# dig_ac230.net
KiCad netlist of a schematic drawn in EAGLE
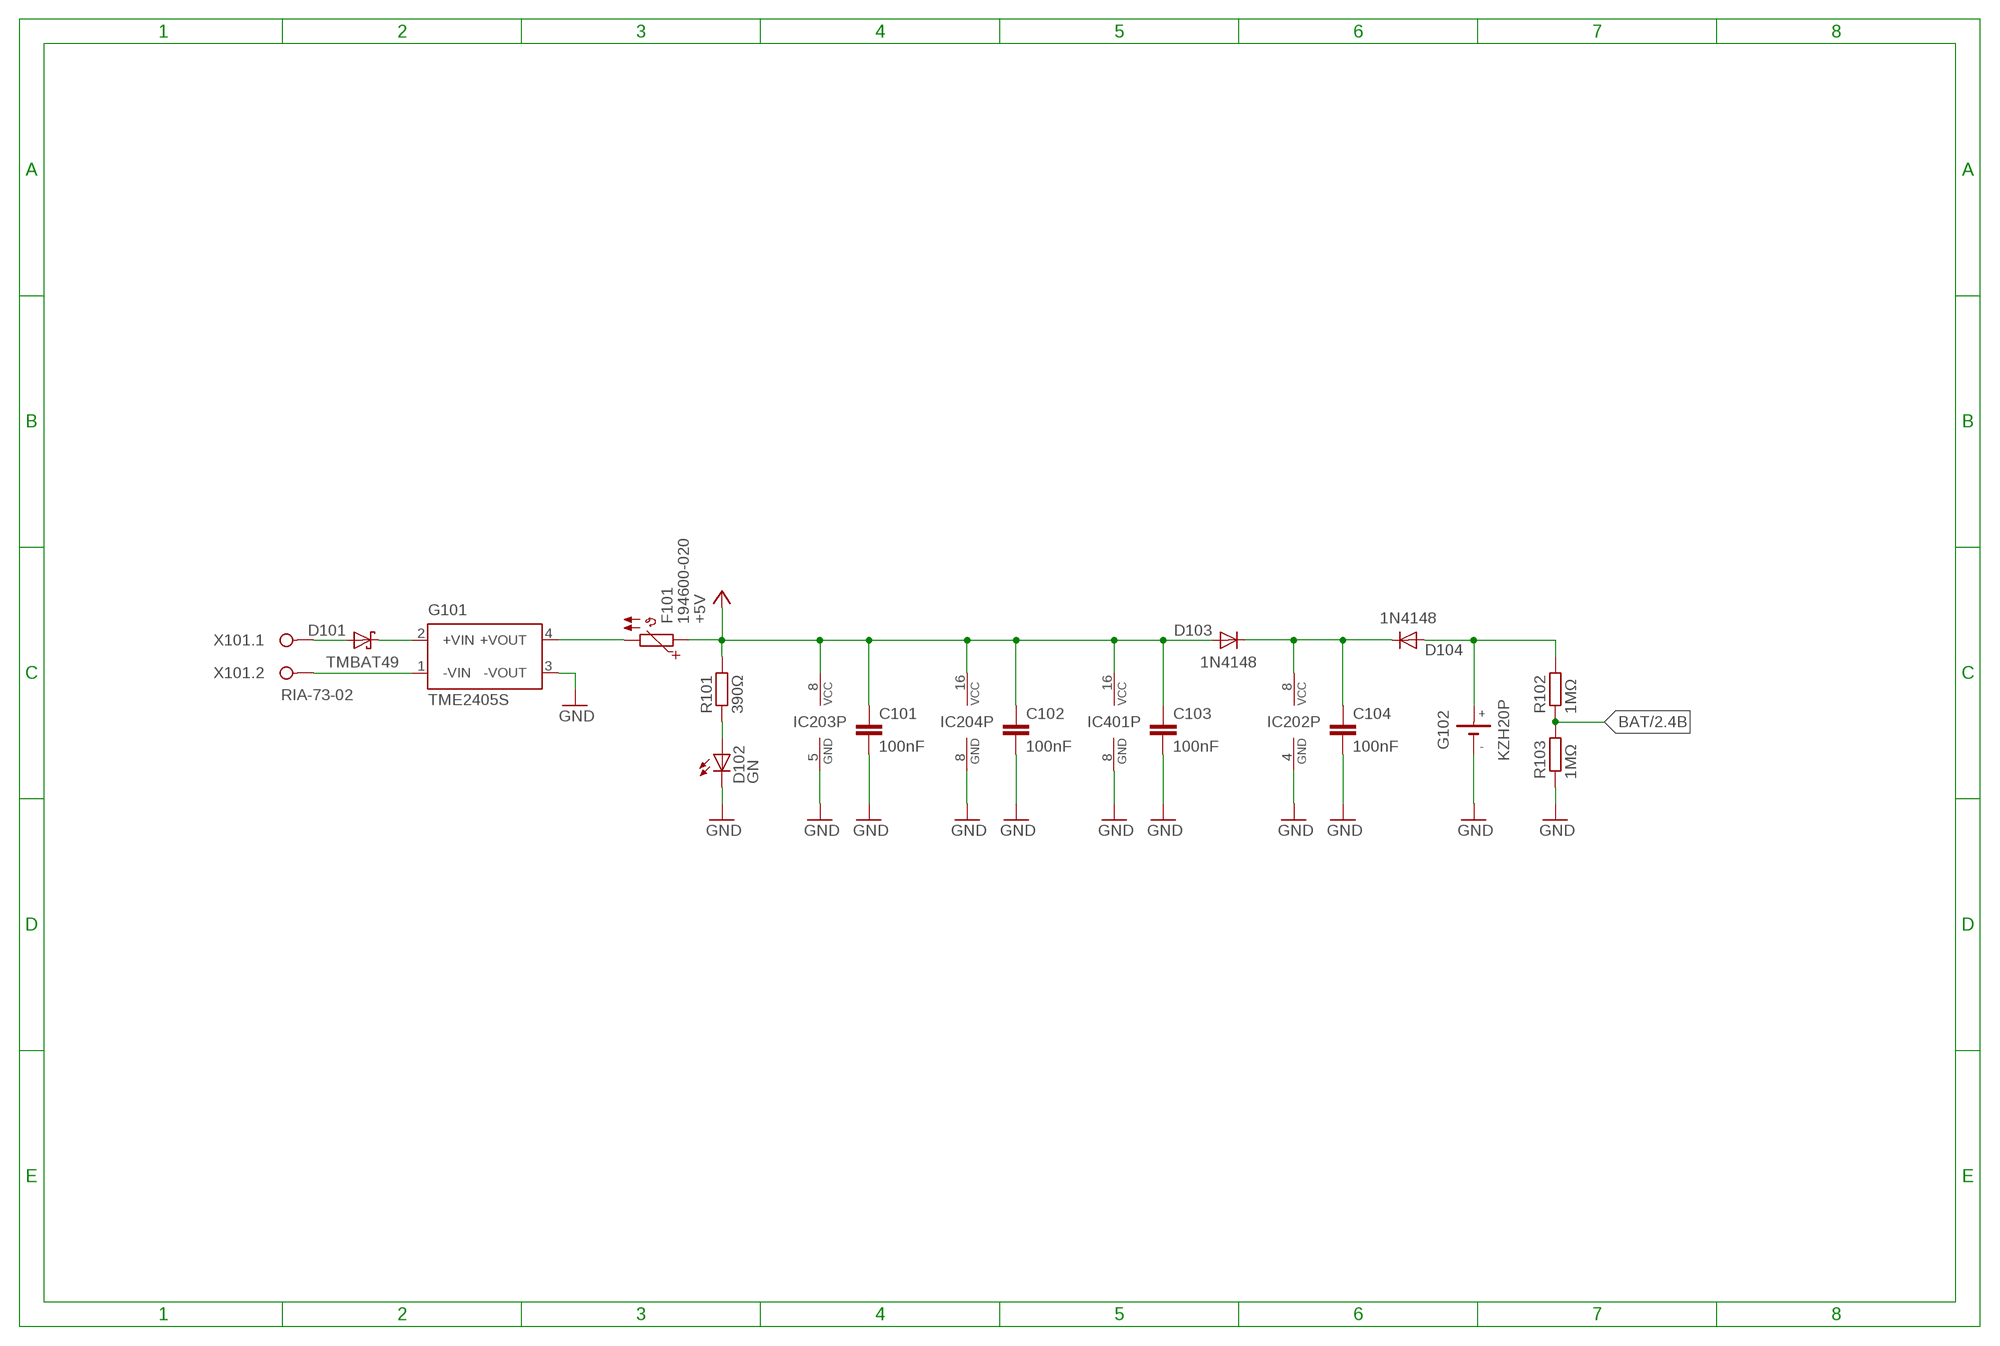
[diagram p0: schematic, sheet 1]
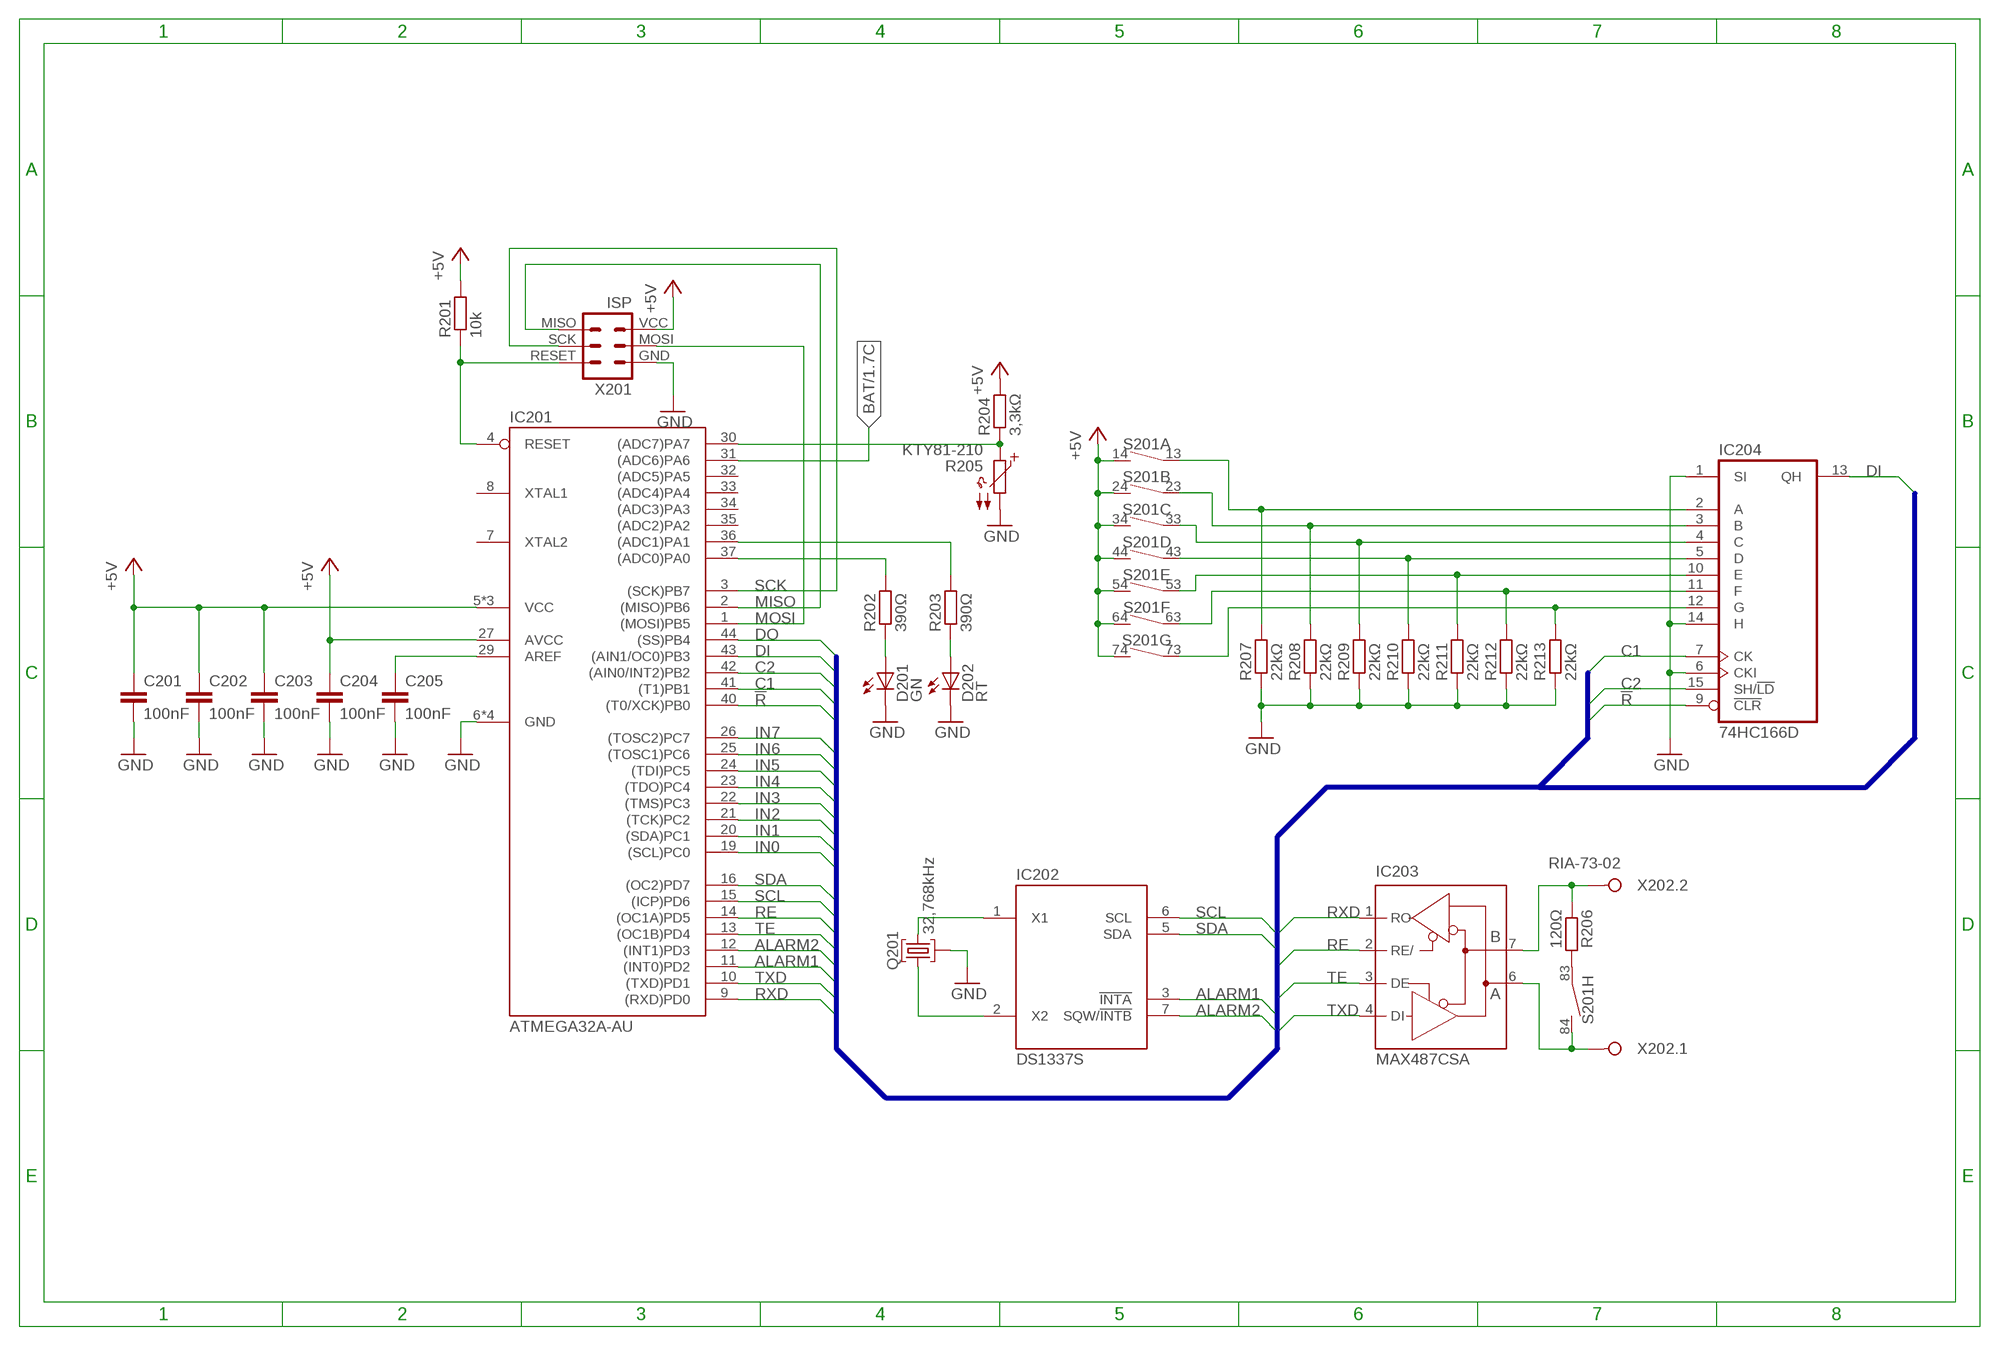
[diagram p1: schematic, sheet 2]
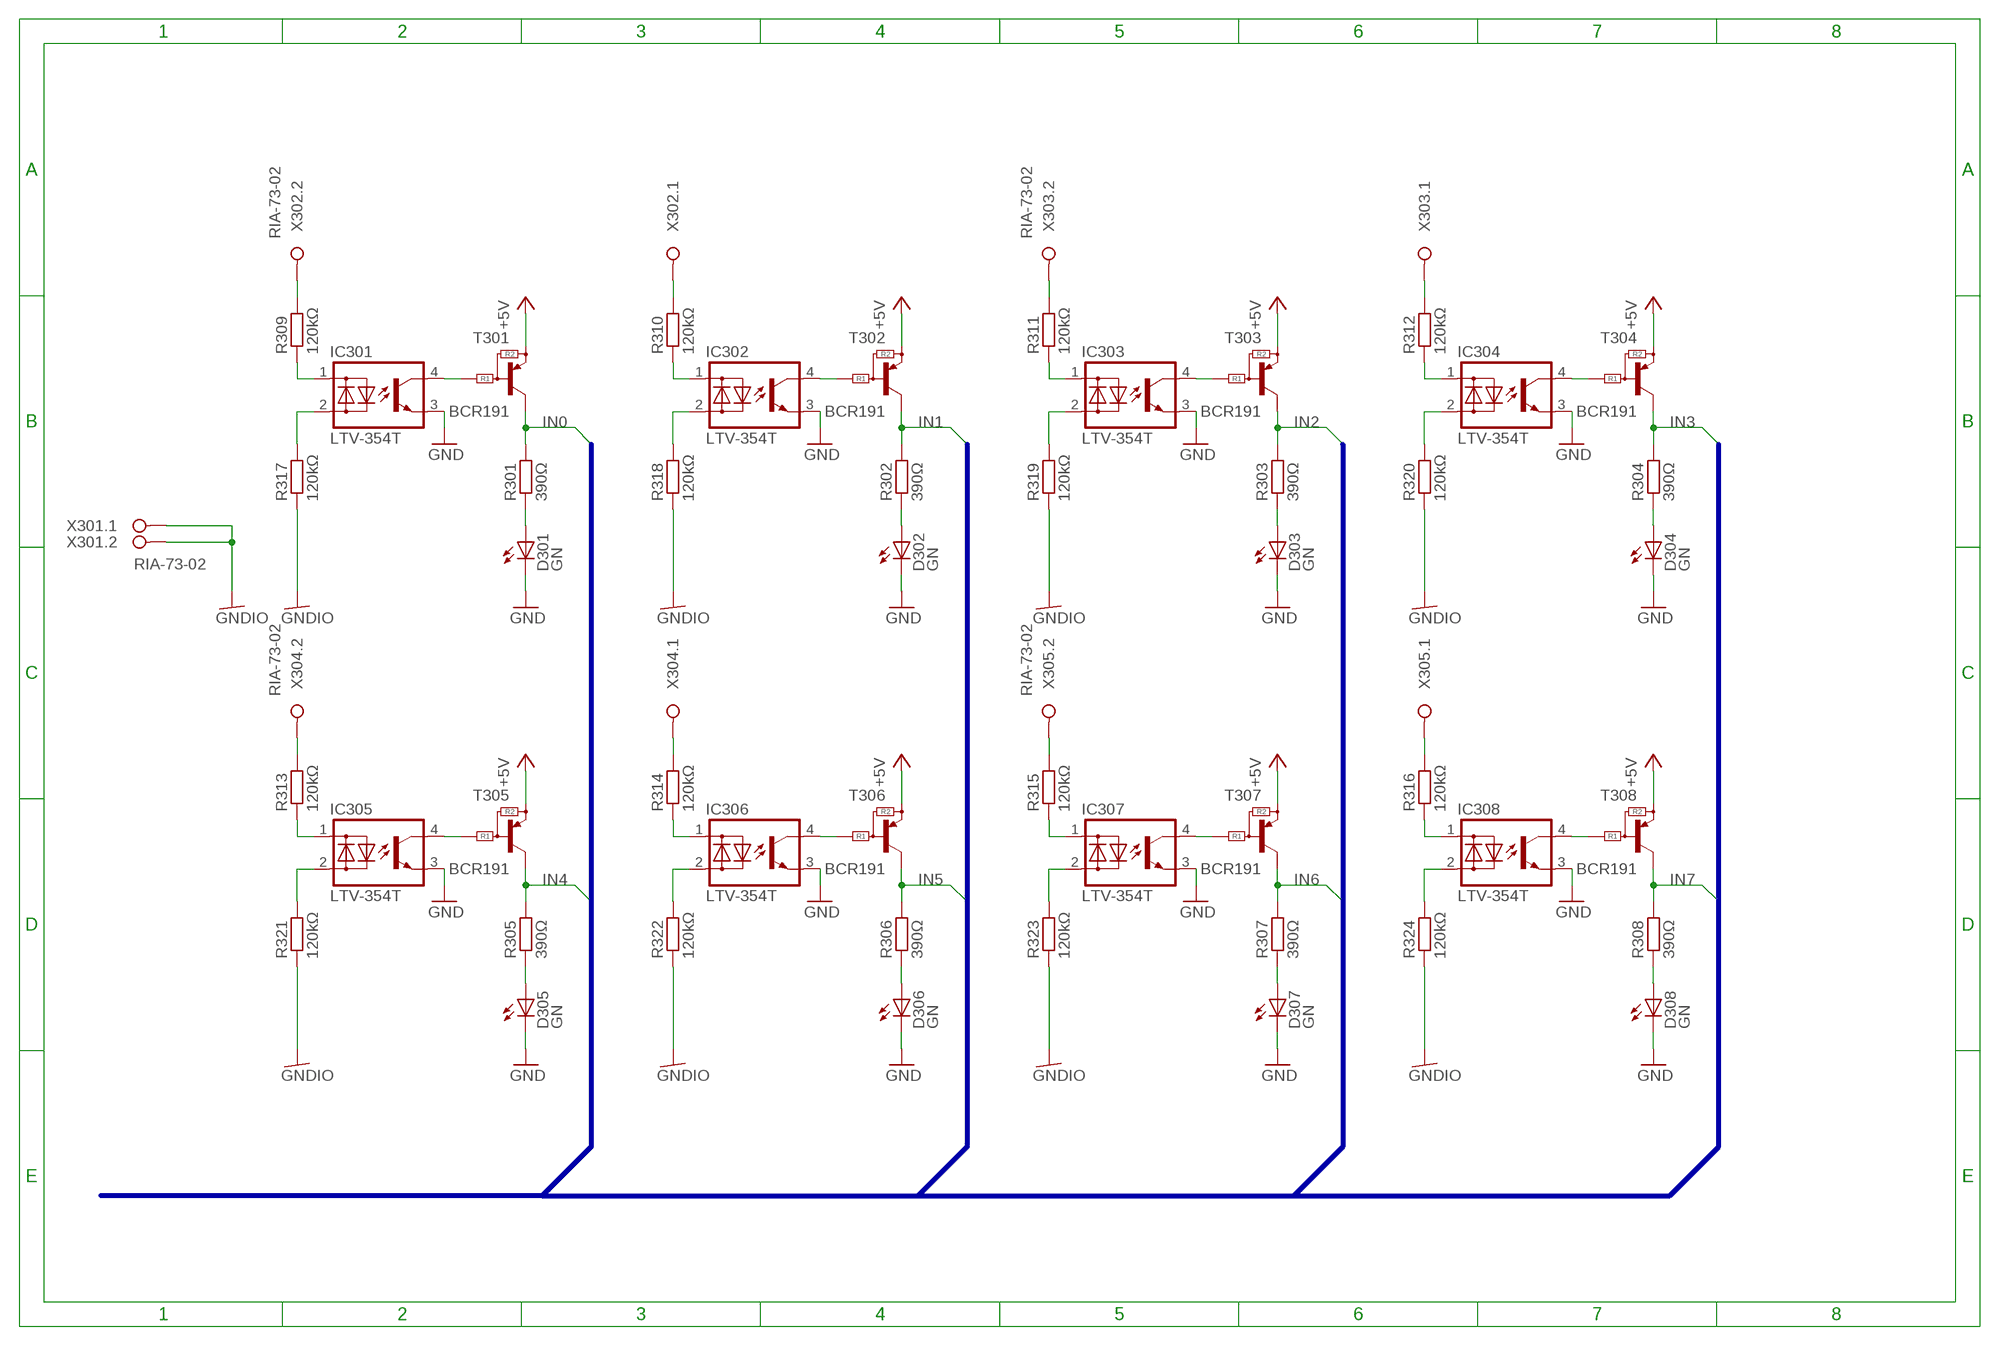
[diagram p2: schematic, sheet 3]
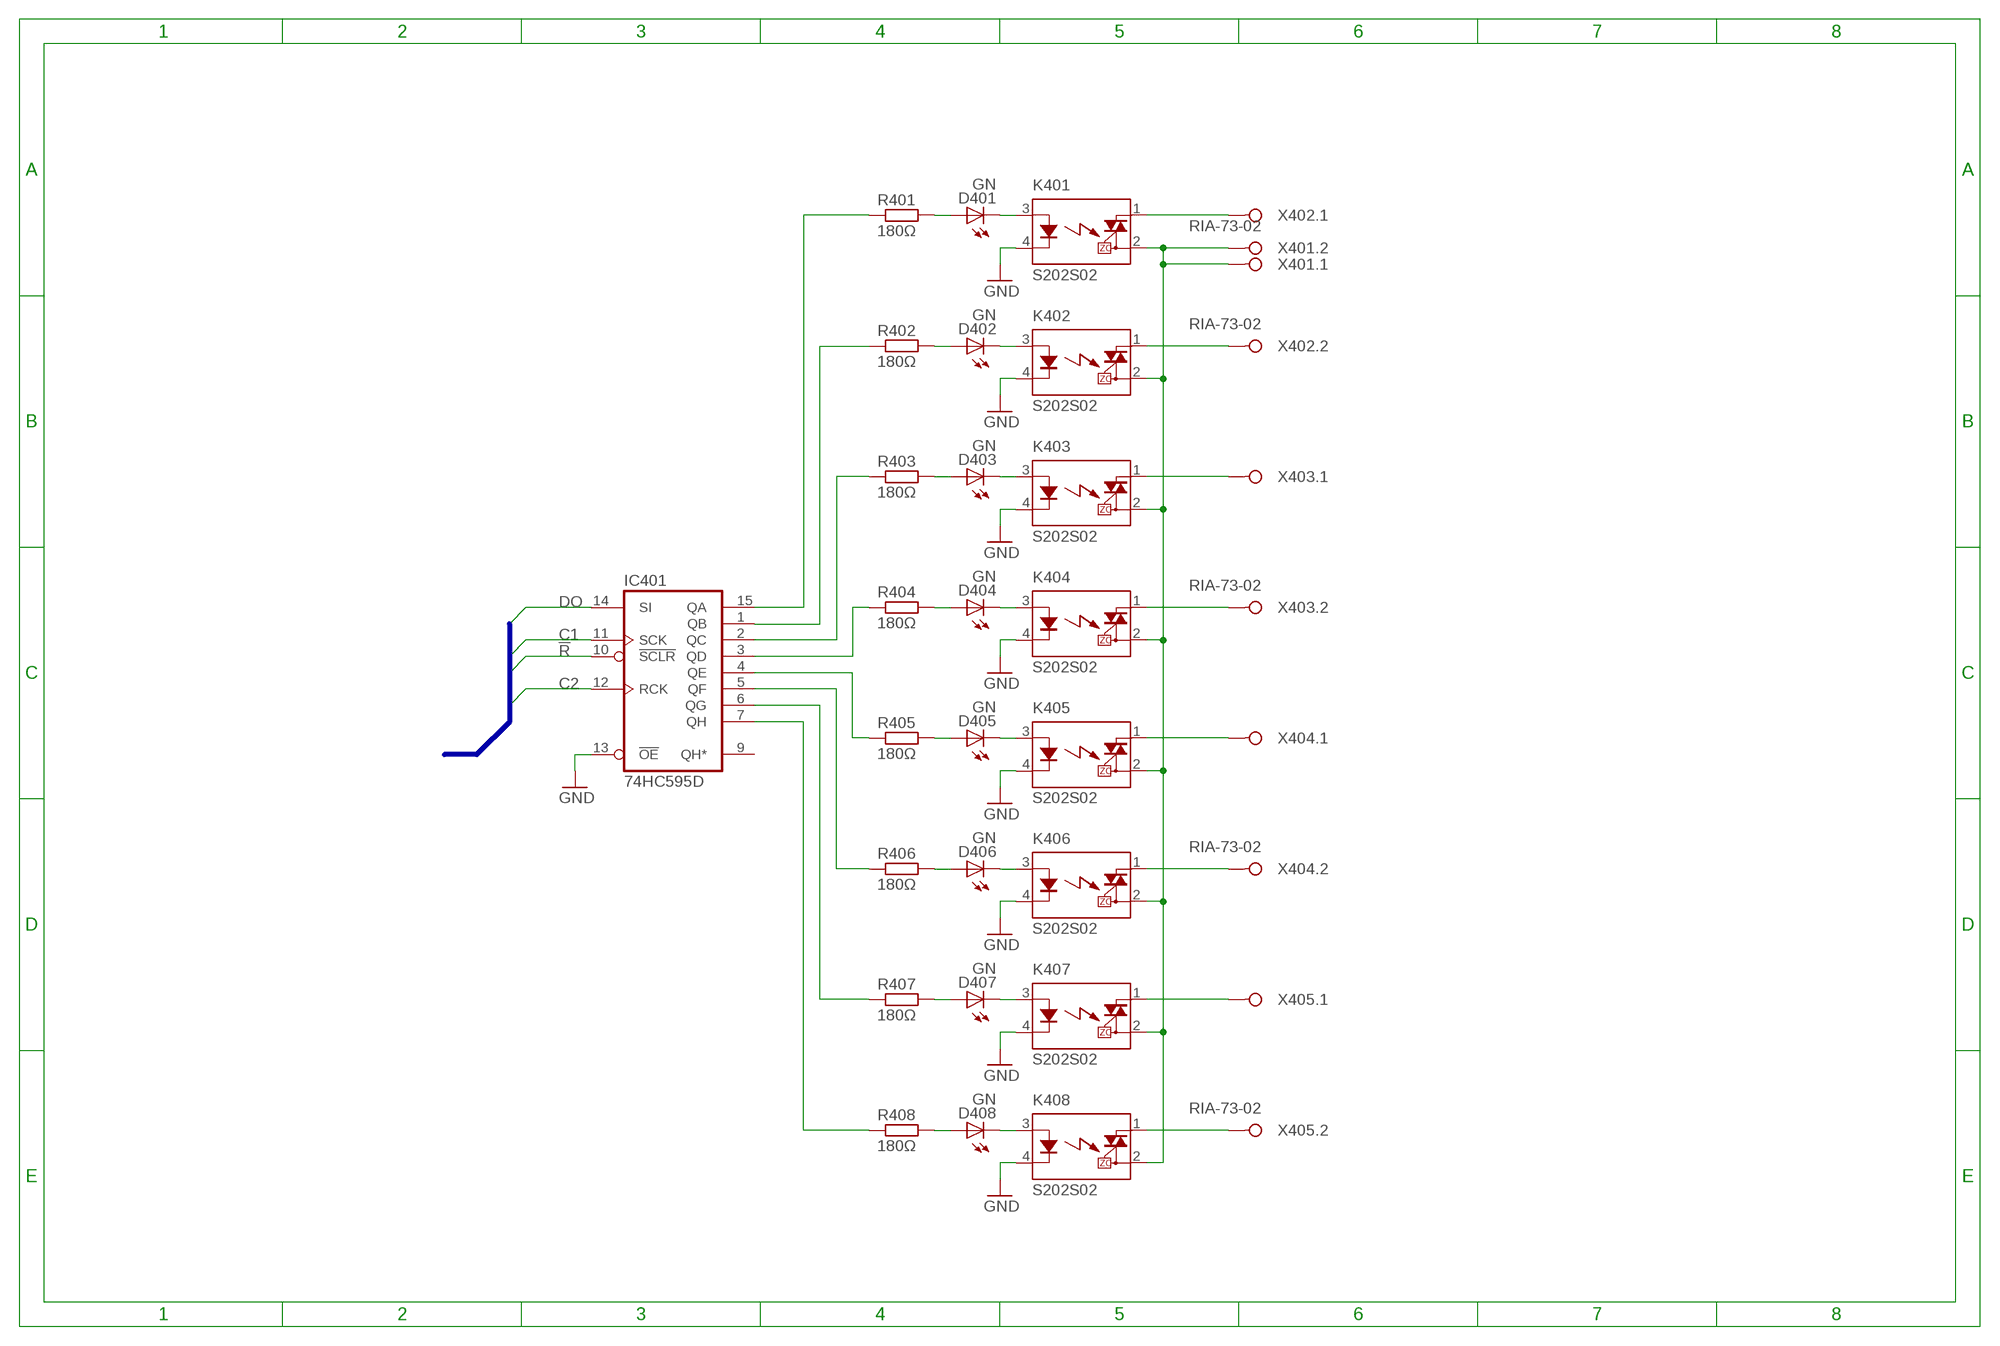
[diagram p3: schematic, sheet 4]

(export (version "E")
  (design (tool "Eeschema 10.0.6"))
  (components
    (comp (ref "C101")
      (value "100nF")
      (footprint "eagle-import:CHIP_0805")
      (libsource (lib "eagle-import") (part "C_0805"))
    )
    (comp (ref "C102")
      (value "100nF")
      (footprint "eagle-import:CHIP_0805")
      (libsource (lib "eagle-import") (part "C_0805"))
    )
    (comp (ref "C103")
      (value "100nF")
      (footprint "eagle-import:CHIP_0805")
      (libsource (lib "eagle-import") (part "C_0805"))
    )
    (comp (ref "C104")
      (value "100nF")
      (footprint "eagle-import:CHIP_0805")
      (libsource (lib "eagle-import") (part "C_0805"))
    )
    (comp (ref "D101")
      (value "TMBAT49")
      (footprint "eagle-import:MELF")
      (libsource (lib "eagle-import") (part "SHOTKY-DIODE-MELF"))
    )
    (comp (ref "D102")
      (value "GN")
      (footprint "eagle-import:LED3MM")
      (libsource (lib "eagle-import") (part "LED3MM"))
    )
    (comp (ref "D103")
      (value "1N4148")
      (footprint "eagle-import:MINIMELF")
      (libsource (lib "eagle-import") (part "DIODE-MINIMELF"))
    )
    (comp (ref "D104")
      (value "1N4148")
      (footprint "eagle-import:MINIMELF")
      (libsource (lib "eagle-import") (part "DIODE-MINIMELF"))
    )
    (comp (ref "F101")
      (value "194600-020")
      (footprint "eagle-import:CHIP_1812")
      (libsource (lib "eagle-import") (part "194600-020"))
    )
    (comp (ref "G101")
      (value "TME2405S")
      (footprint "eagle-import:TME-24V")
      (fields
        (field (name "MPN") "TME 2405S")
        (field (name "MPN_1") "TME 2405S")
        (field (name "OC_FARNELL") "1007547")
        (field (name "OC_NEWARK") "51R5329")
      )
      (libsource (lib "eagle-import") (part "TME?2405S"))
    )
    (comp (ref "G102")
      (value "KZH20P")
      (footprint "eagle-import:KZH20P")
      (libsource (lib "eagle-import") (part "KZH20P"))
    )
    (comp (ref "IC202")
      (value "DS1337S")
      (footprint "eagle-import:SOP08_127")
      (libsource (lib "eagle-import") (part "DS1337S"))
    )
    (comp (ref "IC203")
      (value "MAX487CSA")
      (footprint "eagle-import:SOP08_127")
      (libsource (lib "eagle-import") (part "MAX48CSA7"))
    )
    (comp (ref "IC204")
      (value "74HC166D")
      (footprint "eagle-import:SOP16_127")
      (libsource (lib "eagle-import") (part "74166DHC"))
    )
    (comp (ref "IC401")
      (value "74HC595D")
      (footprint "eagle-import:SOP16_127")
      (libsource (lib "eagle-import") (part "74595DHC"))
    )
    (comp (ref "R101")
      (value "390Ω")
      (footprint "eagle-import:CHIP_0805")
      (libsource (lib "eagle-import") (part "R_0805"))
    )
    (comp (ref "R102")
      (value "1MΩ")
      (footprint "eagle-import:CHIP_0805")
      (libsource (lib "eagle-import") (part "R_0805"))
    )
    (comp (ref "R103")
      (value "1MΩ")
      (footprint "eagle-import:CHIP_0805")
      (libsource (lib "eagle-import") (part "R_0805"))
    )
    (comp (ref "X101")
      (value "RIA-73-02")
      (footprint "eagle-import:RIA-73-02")
      (libsource (lib "eagle-import") (part "RIA-73-02"))
    )
    (comp (ref "C201")
      (value "100nF")
      (footprint "eagle-import:CHIP_0805")
      (libsource (lib "eagle-import") (part "C_0805"))
    )
    (comp (ref "C202")
      (value "100nF")
      (footprint "eagle-import:CHIP_0805")
      (libsource (lib "eagle-import") (part "C_0805"))
    )
    (comp (ref "C203")
      (value "100nF")
      (footprint "eagle-import:CHIP_0805")
      (libsource (lib "eagle-import") (part "C_0805"))
    )
    (comp (ref "C204")
      (value "100nF")
      (footprint "eagle-import:CHIP_0805")
      (libsource (lib "eagle-import") (part "C_0805"))
    )
    (comp (ref "C205")
      (value "100nF")
      (footprint "eagle-import:CHIP_0805")
      (libsource (lib "eagle-import") (part "C_0805"))
    )
    (comp (ref "D201")
      (value "GN")
      (footprint "eagle-import:LED3MM")
      (libsource (lib "eagle-import") (part "LED3MM"))
    )
    (comp (ref "D202")
      (value "RT")
      (footprint "eagle-import:LED3MM")
      (libsource (lib "eagle-import") (part "LED3MM"))
    )
    (comp (ref "IC201")
      (value "ATMEGA32A-AU")
      (footprint "eagle-import:QFP44_08")
      (libsource (lib "eagle-import") (part "ATMEGA32A-AU"))
    )
    (comp (ref "Q201")
      (value "32,768kHz")
      (footprint "eagle-import:MS1V-T1K")
      (libsource (lib "eagle-import") (part "QM_"))
    )
    (comp (ref "R201")
      (value "10k")
      (footprint "eagle-import:CHIP_0805")
      (libsource (lib "eagle-import") (part "R_0805"))
    )
    (comp (ref "R202")
      (value "390Ω")
      (footprint "eagle-import:CHIP_0805")
      (libsource (lib "eagle-import") (part "R_0805"))
    )
    (comp (ref "R203")
      (value "390Ω")
      (footprint "eagle-import:CHIP_0805")
      (libsource (lib "eagle-import") (part "R_0805"))
    )
    (comp (ref "R204")
      (value "3,3kΩ")
      (footprint "eagle-import:CHIP_0805")
      (libsource (lib "eagle-import") (part "R_0805"))
    )
    (comp (ref "R205")
      (value "KTY81-210")
      (footprint "eagle-import:TO92")
      (libsource (lib "eagle-import") (part "KTY81-210"))
    )
    (comp (ref "R206")
      (value "120Ω")
      (footprint "eagle-import:CHIP_0805")
      (libsource (lib "eagle-import") (part "R_0805"))
    )
    (comp (ref "R207")
      (value "22kΩ")
      (footprint "eagle-import:CHIP_0805")
      (libsource (lib "eagle-import") (part "R_0805"))
    )
    (comp (ref "R208")
      (value "22kΩ")
      (footprint "eagle-import:CHIP_0805")
      (libsource (lib "eagle-import") (part "R_0805"))
    )
    (comp (ref "R209")
      (value "22kΩ")
      (footprint "eagle-import:CHIP_0805")
      (libsource (lib "eagle-import") (part "R_0805"))
    )
    (comp (ref "R210")
      (value "22kΩ")
      (footprint "eagle-import:CHIP_0805")
      (libsource (lib "eagle-import") (part "R_0805"))
    )
    (comp (ref "R211")
      (value "22kΩ")
      (footprint "eagle-import:CHIP_0805")
      (libsource (lib "eagle-import") (part "R_0805"))
    )
    (comp (ref "R212")
      (value "22kΩ")
      (footprint "eagle-import:CHIP_0805")
      (libsource (lib "eagle-import") (part "R_0805"))
    )
    (comp (ref "R213")
      (value "22kΩ")
      (footprint "eagle-import:CHIP_0805")
      (libsource (lib "eagle-import") (part "R_0805"))
    )
    (comp (ref "S201")
      (value "DP08")
      (footprint "eagle-import:DP08")
      (libsource (lib "eagle-import") (part "DP08"))
    )
    (comp (ref "X201")
      (value "ISP")
      (footprint "eagle-import:ML6L")
      (libsource (lib "eagle-import") (part "AVR_ISP6L"))
    )
    (comp (ref "X202")
      (value "RIA-73-02")
      (footprint "eagle-import:RIA-73-02")
      (libsource (lib "eagle-import") (part "RIA-73-02"))
    )
    (comp (ref "D301")
      (value "GN")
      (footprint "eagle-import:LED3MM")
      (libsource (lib "eagle-import") (part "LED3MM"))
    )
    (comp (ref "D302")
      (value "GN")
      (footprint "eagle-import:LED3MM")
      (libsource (lib "eagle-import") (part "LED3MM"))
    )
    (comp (ref "D303")
      (value "GN")
      (footprint "eagle-import:LED3MM")
      (libsource (lib "eagle-import") (part "LED3MM"))
    )
    (comp (ref "D304")
      (value "GN")
      (footprint "eagle-import:LED3MM")
      (libsource (lib "eagle-import") (part "LED3MM"))
    )
    (comp (ref "D305")
      (value "GN")
      (footprint "eagle-import:LED3MM")
      (libsource (lib "eagle-import") (part "LED3MM"))
    )
    (comp (ref "D306")
      (value "GN")
      (footprint "eagle-import:LED3MM")
      (libsource (lib "eagle-import") (part "LED3MM"))
    )
    (comp (ref "D307")
      (value "GN")
      (footprint "eagle-import:LED3MM")
      (libsource (lib "eagle-import") (part "LED3MM"))
    )
    (comp (ref "D308")
      (value "GN")
      (footprint "eagle-import:LED3MM")
      (libsource (lib "eagle-import") (part "LED3MM"))
    )
    (comp (ref "IC301")
      (value "LTV-354T")
      (footprint "eagle-import:SOP04_254")
      (libsource (lib "eagle-import") (part "LTV-354T"))
    )
    (comp (ref "IC302")
      (value "LTV-354T")
      (footprint "eagle-import:SOP04_254")
      (libsource (lib "eagle-import") (part "LTV-354T"))
    )
    (comp (ref "IC303")
      (value "LTV-354T")
      (footprint "eagle-import:SOP04_254")
      (libsource (lib "eagle-import") (part "LTV-354T"))
    )
    (comp (ref "IC304")
      (value "LTV-354T")
      (footprint "eagle-import:SOP04_254")
      (libsource (lib "eagle-import") (part "LTV-354T"))
    )
    (comp (ref "IC305")
      (value "LTV-354T")
      (footprint "eagle-import:SOP04_254")
      (libsource (lib "eagle-import") (part "LTV-354T"))
    )
    (comp (ref "IC306")
      (value "LTV-354T")
      (footprint "eagle-import:SOP04_254")
      (libsource (lib "eagle-import") (part "LTV-354T"))
    )
    (comp (ref "IC307")
      (value "LTV-354T")
      (footprint "eagle-import:SOP04_254")
      (libsource (lib "eagle-import") (part "LTV-354T"))
    )
    (comp (ref "IC308")
      (value "LTV-354T")
      (footprint "eagle-import:SOP04_254")
      (libsource (lib "eagle-import") (part "LTV-354T"))
    )
    (comp (ref "R301")
      (value "390Ω")
      (footprint "eagle-import:CHIP_0805")
      (libsource (lib "eagle-import") (part "R_0805"))
    )
    (comp (ref "R302")
      (value "390Ω")
      (footprint "eagle-import:CHIP_0805")
      (libsource (lib "eagle-import") (part "R_0805"))
    )
    (comp (ref "R303")
      (value "390Ω")
      (footprint "eagle-import:CHIP_0805")
      (libsource (lib "eagle-import") (part "R_0805"))
    )
    (comp (ref "R304")
      (value "390Ω")
      (footprint "eagle-import:CHIP_0805")
      (libsource (lib "eagle-import") (part "R_0805"))
    )
    (comp (ref "R305")
      (value "390Ω")
      (footprint "eagle-import:CHIP_0805")
      (libsource (lib "eagle-import") (part "R_0805"))
    )
    (comp (ref "R306")
      (value "390Ω")
      (footprint "eagle-import:CHIP_0805")
      (libsource (lib "eagle-import") (part "R_0805"))
    )
    (comp (ref "R307")
      (value "390Ω")
      (footprint "eagle-import:CHIP_0805")
      (libsource (lib "eagle-import") (part "R_0805"))
    )
    (comp (ref "R308")
      (value "390Ω")
      (footprint "eagle-import:CHIP_0805")
      (libsource (lib "eagle-import") (part "R_0805"))
    )
    (comp (ref "R309")
      (value "120kΩ")
      (footprint "eagle-import:CHIP_1206")
      (libsource (lib "eagle-import") (part "R_1206"))
    )
    (comp (ref "R310")
      (value "120kΩ")
      (footprint "eagle-import:CHIP_1206")
      (libsource (lib "eagle-import") (part "R_1206"))
    )
    (comp (ref "R311")
      (value "120kΩ")
      (footprint "eagle-import:CHIP_1206")
      (libsource (lib "eagle-import") (part "R_1206"))
    )
    (comp (ref "R312")
      (value "120kΩ")
      (footprint "eagle-import:CHIP_1206")
      (libsource (lib "eagle-import") (part "R_1206"))
    )
    (comp (ref "R313")
      (value "120kΩ")
      (footprint "eagle-import:CHIP_1206")
      (libsource (lib "eagle-import") (part "R_1206"))
    )
    (comp (ref "R314")
      (value "120kΩ")
      (footprint "eagle-import:CHIP_1206")
      (libsource (lib "eagle-import") (part "R_1206"))
    )
    (comp (ref "R315")
      (value "120kΩ")
      (footprint "eagle-import:CHIP_1206")
      (libsource (lib "eagle-import") (part "R_1206"))
    )
    (comp (ref "R316")
      (value "120kΩ")
      (footprint "eagle-import:CHIP_1206")
      (libsource (lib "eagle-import") (part "R_1206"))
    )
    (comp (ref "R317")
      (value "120kΩ")
      (footprint "eagle-import:CHIP_1206")
      (libsource (lib "eagle-import") (part "R_1206"))
    )
    (comp (ref "R318")
      (value "120kΩ")
      (footprint "eagle-import:CHIP_1206")
      (libsource (lib "eagle-import") (part "R_1206"))
    )
    (comp (ref "R319")
      (value "120kΩ")
      (footprint "eagle-import:CHIP_1206")
      (libsource (lib "eagle-import") (part "R_1206"))
    )
    (comp (ref "R320")
      (value "120kΩ")
      (footprint "eagle-import:CHIP_1206")
      (libsource (lib "eagle-import") (part "R_1206"))
    )
    (comp (ref "R321")
      (value "120kΩ")
      (footprint "eagle-import:CHIP_1206")
      (libsource (lib "eagle-import") (part "R_1206"))
    )
    (comp (ref "R322")
      (value "120kΩ")
      (footprint "eagle-import:CHIP_1206")
      (libsource (lib "eagle-import") (part "R_1206"))
    )
    (comp (ref "R323")
      (value "120kΩ")
      (footprint "eagle-import:CHIP_1206")
      (libsource (lib "eagle-import") (part "R_1206"))
    )
    (comp (ref "R324")
      (value "120kΩ")
      (footprint "eagle-import:CHIP_1206")
      (libsource (lib "eagle-import") (part "R_1206"))
    )
    (comp (ref "T301")
      (value "BCR191")
      (footprint "eagle-import:SOT23")
      (libsource (lib "eagle-import") (part "PNP2R-SOT23-BEC"))
    )
    (comp (ref "T302")
      (value "BCR191")
      (footprint "eagle-import:SOT23")
      (libsource (lib "eagle-import") (part "PNP2R-SOT23-BEC"))
    )
    (comp (ref "T303")
      (value "BCR191")
      (footprint "eagle-import:SOT23")
      (libsource (lib "eagle-import") (part "PNP2R-SOT23-BEC"))
    )
    (comp (ref "T304")
      (value "BCR191")
      (footprint "eagle-import:SOT23")
      (libsource (lib "eagle-import") (part "PNP2R-SOT23-BEC"))
    )
    (comp (ref "T305")
      (value "BCR191")
      (footprint "eagle-import:SOT23")
      (libsource (lib "eagle-import") (part "PNP2R-SOT23-BEC"))
    )
    (comp (ref "T306")
      (value "BCR191")
      (footprint "eagle-import:SOT23")
      (libsource (lib "eagle-import") (part "PNP2R-SOT23-BEC"))
    )
    (comp (ref "T307")
      (value "BCR191")
      (footprint "eagle-import:SOT23")
      (libsource (lib "eagle-import") (part "PNP2R-SOT23-BEC"))
    )
    (comp (ref "T308")
      (value "BCR191")
      (footprint "eagle-import:SOT23")
      (libsource (lib "eagle-import") (part "PNP2R-SOT23-BEC"))
    )
    (comp (ref "X301")
      (value "RIA-73-02")
      (footprint "eagle-import:RIA-73-02")
      (libsource (lib "eagle-import") (part "RIA-73-02"))
    )
    (comp (ref "X302")
      (value "RIA-73-02")
      (footprint "eagle-import:RIA-73-02")
      (libsource (lib "eagle-import") (part "RIA-73-02"))
    )
    (comp (ref "X303")
      (value "RIA-73-02")
      (footprint "eagle-import:RIA-73-02")
      (libsource (lib "eagle-import") (part "RIA-73-02"))
    )
    (comp (ref "X304")
      (value "RIA-73-02")
      (footprint "eagle-import:RIA-73-02")
      (libsource (lib "eagle-import") (part "RIA-73-02"))
    )
    (comp (ref "X305")
      (value "RIA-73-02")
      (footprint "eagle-import:RIA-73-02")
      (libsource (lib "eagle-import") (part "RIA-73-02"))
    )
    (comp (ref "D401")
      (value "GN")
      (footprint "eagle-import:LED3MM")
      (libsource (lib "eagle-import") (part "LED3MM"))
    )
    (comp (ref "D402")
      (value "GN")
      (footprint "eagle-import:LED3MM")
      (libsource (lib "eagle-import") (part "LED3MM"))
    )
    (comp (ref "D403")
      (value "GN")
      (footprint "eagle-import:LED3MM")
      (libsource (lib "eagle-import") (part "LED3MM"))
    )
    (comp (ref "D404")
      (value "GN")
      (footprint "eagle-import:LED3MM")
      (libsource (lib "eagle-import") (part "LED3MM"))
    )
    (comp (ref "D405")
      (value "GN")
      (footprint "eagle-import:LED3MM")
      (libsource (lib "eagle-import") (part "LED3MM"))
    )
    (comp (ref "D406")
      (value "GN")
      (footprint "eagle-import:LED3MM")
      (libsource (lib "eagle-import") (part "LED3MM"))
    )
    (comp (ref "D407")
      (value "GN")
      (footprint "eagle-import:LED3MM")
      (libsource (lib "eagle-import") (part "LED3MM"))
    )
    (comp (ref "D408")
      (value "GN")
      (footprint "eagle-import:LED3MM")
      (libsource (lib "eagle-import") (part "LED3MM"))
    )
    (comp (ref "K401")
      (value "S202S02")
      (footprint "eagle-import:SIP4")
      (libsource (lib "eagle-import") (part "S02S022"))
    )
    (comp (ref "K402")
      (value "S202S02")
      (footprint "eagle-import:SIP4")
      (libsource (lib "eagle-import") (part "S02S022"))
    )
    (comp (ref "K403")
      (value "S202S02")
      (footprint "eagle-import:SIP4")
      (libsource (lib "eagle-import") (part "S02S022"))
    )
    (comp (ref "K404")
      (value "S202S02")
      (footprint "eagle-import:SIP4")
      (libsource (lib "eagle-import") (part "S02S022"))
    )
    (comp (ref "K405")
      (value "S202S02")
      (footprint "eagle-import:SIP4")
      (libsource (lib "eagle-import") (part "S02S022"))
    )
    (comp (ref "K406")
      (value "S202S02")
      (footprint "eagle-import:SIP4")
      (libsource (lib "eagle-import") (part "S02S022"))
    )
    (comp (ref "K407")
      (value "S202S02")
      (footprint "eagle-import:SIP4")
      (libsource (lib "eagle-import") (part "S02S022"))
    )
    (comp (ref "K408")
      (value "S202S02")
      (footprint "eagle-import:SIP4")
      (libsource (lib "eagle-import") (part "S02S022"))
    )
    (comp (ref "R401")
      (value "180Ω")
      (footprint "eagle-import:CHIP_0805")
      (libsource (lib "eagle-import") (part "R_0805"))
    )
    (comp (ref "R402")
      (value "180Ω")
      (footprint "eagle-import:CHIP_0805")
      (libsource (lib "eagle-import") (part "R_0805"))
    )
    (comp (ref "R403")
      (value "180Ω")
      (footprint "eagle-import:CHIP_0805")
      (libsource (lib "eagle-import") (part "R_0805"))
    )
    (comp (ref "R404")
      (value "180Ω")
      (footprint "eagle-import:CHIP_0805")
      (libsource (lib "eagle-import") (part "R_0805"))
    )
    (comp (ref "R405")
      (value "180Ω")
      (footprint "eagle-import:CHIP_0805")
      (libsource (lib "eagle-import") (part "R_0805"))
    )
    (comp (ref "R406")
      (value "180Ω")
      (footprint "eagle-import:CHIP_0805")
      (libsource (lib "eagle-import") (part "R_0805"))
    )
    (comp (ref "R407")
      (value "180Ω")
      (footprint "eagle-import:CHIP_0805")
      (libsource (lib "eagle-import") (part "R_0805"))
    )
    (comp (ref "R408")
      (value "180Ω")
      (footprint "eagle-import:CHIP_0805")
      (libsource (lib "eagle-import") (part "R_0805"))
    )
    (comp (ref "X401")
      (value "RIA-73-02")
      (footprint "eagle-import:RIA-73-02")
      (libsource (lib "eagle-import") (part "RIA-73-02"))
    )
    (comp (ref "X402")
      (value "RIA-73-02")
      (footprint "eagle-import:RIA-73-02")
      (libsource (lib "eagle-import") (part "RIA-73-02"))
    )
    (comp (ref "X403")
      (value "RIA-73-02")
      (footprint "eagle-import:RIA-73-02")
      (libsource (lib "eagle-import") (part "RIA-73-02"))
    )
    (comp (ref "X404")
      (value "RIA-73-02")
      (footprint "eagle-import:RIA-73-02")
      (libsource (lib "eagle-import") (part "RIA-73-02"))
    )
    (comp (ref "X405")
      (value "RIA-73-02")
      (footprint "eagle-import:RIA-73-02")
      (libsource (lib "eagle-import") (part "RIA-73-02"))
    )
  )
  (nets
    (net (code "1") (name "+5V") (class "Default")
      (node (ref "C101") (pin "1") (pinfunction "1_1") (pintype "passive"))
      (node (ref "C102") (pin "1") (pinfunction "1_1") (pintype "passive"))
      (node (ref "C103") (pin "1") (pinfunction "1_1") (pintype "passive"))
      (node (ref "C201") (pin "1") (pinfunction "1_1") (pintype "passive"))
      (node (ref "C202") (pin "1") (pinfunction "1_1") (pintype "passive"))
      (node (ref "C203") (pin "1") (pinfunction "1_1") (pintype "passive"))
      (node (ref "C204") (pin "1") (pinfunction "1_1") (pintype "passive"))
      (node (ref "D103") (pin "A") (pinfunction "A_A") (pintype "passive"))
      (node (ref "F101") (pin "1") (pinfunction "1_1") (pintype "passive"))
      (node (ref "IC201") (pin "17") (pinfunction "VCC_17") (pintype "power_in"))
      (node (ref "IC201") (pin "27") (pinfunction "AVCC_27") (pintype "power_in"))
      (node (ref "IC201") (pin "38") (pinfunction "VCC_38") (pintype "power_in"))
      (node (ref "IC201") (pin "5") (pinfunction "VCC_5") (pintype "power_in"))
      (node (ref "IC203") (pin "8") (pinfunction "VCC_8") (pintype "power_in"))
      (node (ref "IC204") (pin "16") (pinfunction "VCC_16") (pintype "power_in"))
      (node (ref "IC401") (pin "16") (pinfunction "VCC_16") (pintype "power_in"))
      (node (ref "R101") (pin "2") (pinfunction "2_2") (pintype "passive"))
      (node (ref "R201") (pin "2") (pinfunction "2_2") (pintype "passive"))
      (node (ref "R204") (pin "2") (pinfunction "2_2") (pintype "passive"))
      (node (ref "S201") (pin "14") (pinfunction "4_14") (pintype "passive"))
      (node (ref "S201") (pin "24") (pinfunction "4_24") (pintype "passive"))
      (node (ref "S201") (pin "34") (pinfunction "4_34") (pintype "passive"))
      (node (ref "S201") (pin "44") (pinfunction "4_44") (pintype "passive"))
      (node (ref "S201") (pin "54") (pinfunction "4_54") (pintype "passive"))
      (node (ref "S201") (pin "64") (pinfunction "4_64") (pintype "passive"))
      (node (ref "S201") (pin "74") (pinfunction "4_74") (pintype "passive"))
      (node (ref "T301") (pin "2") (pinfunction "E_2") (pintype "passive"))
      (node (ref "T302") (pin "2") (pinfunction "E_2") (pintype "passive"))
      (node (ref "T303") (pin "2") (pinfunction "E_2") (pintype "passive"))
      (node (ref "T304") (pin "2") (pinfunction "E_2") (pintype "passive"))
      (node (ref "T305") (pin "2") (pinfunction "E_2") (pintype "passive"))
      (node (ref "T306") (pin "2") (pinfunction "E_2") (pintype "passive"))
      (node (ref "T307") (pin "2") (pinfunction "E_2") (pintype "passive"))
      (node (ref "T308") (pin "2") (pinfunction "E_2") (pintype "passive"))
      (node (ref "X201") (pin "VCC") (pinfunction "VCC_VCC") (pintype "passive"))
    )
    (net (code "2") (name "ALARM1") (class "Default")
      (node (ref "IC201") (pin "11") (pinfunction "(INT0)PD2_11") (pintype "bidirectional"))
      (node (ref "IC202") (pin "3") (pinfunction "~{INTA}_3") (pintype "open_collector"))
    )
    (net (code "3") (name "ALARM2") (class "Default")
      (node (ref "IC201") (pin "12") (pinfunction "(INT1)PD3_12") (pintype "bidirectional"))
      (node (ref "IC202") (pin "7") (pinfunction "SQW/~{INTB}_7") (pintype "open_collector"))
    )
    (net (code "4") (name "BAT") (class "Default")
      (node (ref "IC201") (pin "31") (pinfunction "(ADC6)PA6_31") (pintype "bidirectional"))
      (node (ref "R102") (pin "1") (pinfunction "1_1") (pintype "passive"))
      (node (ref "R103") (pin "2") (pinfunction "2_2") (pintype "passive"))
    )
    (net (code "5") (name "C1") (class "Default")
      (node (ref "IC201") (pin "41") (pinfunction "(T1)PB1_41") (pintype "bidirectional"))
      (node (ref "IC204") (pin "7") (pinfunction "CK_7") (pintype "input"))
      (node (ref "IC401") (pin "11") (pinfunction "SCK_11") (pintype "input"))
    )
    (net (code "6") (name "C2") (class "Default")
      (node (ref "IC201") (pin "42") (pinfunction "(AIN0/INT2)PB2_42") (pintype "bidirectional"))
      (node (ref "IC204") (pin "15") (pinfunction "SH/~{LD}_15") (pintype "input"))
      (node (ref "IC401") (pin "12") (pinfunction "RCK_12") (pintype "input"))
    )
    (net (code "7") (name "DI") (class "Default")
      (node (ref "IC201") (pin "43") (pinfunction "(AIN1/OC0)PB3_43") (pintype "bidirectional"))
      (node (ref "IC204") (pin "13") (pinfunction "QH_13") (pintype "output"))
    )
    (net (code "8") (name "DO") (class "Default")
      (node (ref "IC201") (pin "44") (pinfunction "(SS)PB4_44") (pintype "bidirectional"))
      (node (ref "IC401") (pin "14") (pinfunction "SI_14") (pintype "input"))
    )
    (net (code "9") (name "GND") (class "Default")
      (node (ref "C101") (pin "2") (pinfunction "2_2") (pintype "passive"))
      (node (ref "C102") (pin "2") (pinfunction "2_2") (pintype "passive"))
      (node (ref "C103") (pin "2") (pinfunction "2_2") (pintype "passive"))
      (node (ref "C104") (pin "2") (pinfunction "2_2") (pintype "passive"))
      (node (ref "C201") (pin "2") (pinfunction "2_2") (pintype "passive"))
      (node (ref "C202") (pin "2") (pinfunction "2_2") (pintype "passive"))
      (node (ref "C203") (pin "2") (pinfunction "2_2") (pintype "passive"))
      (node (ref "C204") (pin "2") (pinfunction "2_2") (pintype "passive"))
      (node (ref "C205") (pin "2") (pinfunction "2_2") (pintype "passive"))
      (node (ref "D102") (pin "K") (pinfunction "C_K") (pintype "passive"))
      (node (ref "D201") (pin "K") (pinfunction "C_K") (pintype "passive"))
      (node (ref "D202") (pin "K") (pinfunction "C_K") (pintype "passive"))
      (node (ref "D301") (pin "K") (pinfunction "C_K") (pintype "passive"))
      (node (ref "D302") (pin "K") (pinfunction "C_K") (pintype "passive"))
      (node (ref "D303") (pin "K") (pinfunction "C_K") (pintype "passive"))
      (node (ref "D304") (pin "K") (pinfunction "C_K") (pintype "passive"))
      (node (ref "D305") (pin "K") (pinfunction "C_K") (pintype "passive"))
      (node (ref "D306") (pin "K") (pinfunction "C_K") (pintype "passive"))
      (node (ref "D307") (pin "K") (pinfunction "C_K") (pintype "passive"))
      (node (ref "D308") (pin "K") (pinfunction "C_K") (pintype "passive"))
      (node (ref "G101") (pin "3") (pinfunction "-VOUT_3") (pintype "passive"))
      (node (ref "G102") (pin "N") (pinfunction "-_N") (pintype "passive"))
      (node (ref "IC201") (pin "18") (pinfunction "GND_18") (pintype "power_in"))
      (node (ref "IC201") (pin "28") (pinfunction "GND_28") (pintype "power_in"))
      (node (ref "IC201") (pin "39") (pinfunction "GND_39") (pintype "power_in"))
      (node (ref "IC201") (pin "6") (pinfunction "GND_6") (pintype "power_in"))
      (node (ref "IC202") (pin "4") (pinfunction "GND_4") (pintype "power_in"))
      (node (ref "IC203") (pin "5") (pinfunction "GND_5") (pintype "power_in"))
      (node (ref "IC204") (pin "1") (pinfunction "SI_1") (pintype "input"))
      (node (ref "IC204") (pin "14") (pinfunction "H_14") (pintype "input"))
      (node (ref "IC204") (pin "6") (pinfunction "CKI_6") (pintype "input"))
      (node (ref "IC204") (pin "8") (pinfunction "GND_8") (pintype "power_in"))
      (node (ref "IC301") (pin "3") (pinfunction "E_3") (pintype "passive"))
      (node (ref "IC302") (pin "3") (pinfunction "E_3") (pintype "passive"))
      (node (ref "IC303") (pin "3") (pinfunction "E_3") (pintype "passive"))
      (node (ref "IC304") (pin "3") (pinfunction "E_3") (pintype "passive"))
      (node (ref "IC305") (pin "3") (pinfunction "E_3") (pintype "passive"))
      (node (ref "IC306") (pin "3") (pinfunction "E_3") (pintype "passive"))
      (node (ref "IC307") (pin "3") (pinfunction "E_3") (pintype "passive"))
      (node (ref "IC308") (pin "3") (pinfunction "E_3") (pintype "passive"))
      (node (ref "IC401") (pin "13") (pinfunction "~{OE}_13") (pintype "input"))
      (node (ref "IC401") (pin "8") (pinfunction "GND_8") (pintype "power_in"))
      (node (ref "K401") (pin "4") (pinfunction "K_4") (pintype "passive"))
      (node (ref "K402") (pin "4") (pinfunction "K_4") (pintype "passive"))
      (node (ref "K403") (pin "4") (pinfunction "K_4") (pintype "passive"))
      (node (ref "K404") (pin "4") (pinfunction "K_4") (pintype "passive"))
      (node (ref "K405") (pin "4") (pinfunction "K_4") (pintype "passive"))
      (node (ref "K406") (pin "4") (pinfunction "K_4") (pintype "passive"))
      (node (ref "K407") (pin "4") (pinfunction "K_4") (pintype "passive"))
      (node (ref "K408") (pin "4") (pinfunction "K_4") (pintype "passive"))
      (node (ref "Q201") (pin "G") (pinfunction "G_G") (pintype "passive"))
      (node (ref "R103") (pin "1") (pinfunction "1_1") (pintype "passive"))
      (node (ref "R205") (pin "2") (pinfunction "2_2") (pintype "passive"))
      (node (ref "R207") (pin "1") (pinfunction "1_1") (pintype "passive"))
      (node (ref "R208") (pin "1") (pinfunction "1_1") (pintype "passive"))
      (node (ref "R209") (pin "1") (pinfunction "1_1") (pintype "passive"))
      (node (ref "R210") (pin "1") (pinfunction "1_1") (pintype "passive"))
      (node (ref "R211") (pin "1") (pinfunction "1_1") (pintype "passive"))
      (node (ref "R212") (pin "1") (pinfunction "1_1") (pintype "passive"))
      (node (ref "R213") (pin "1") (pinfunction "1_1") (pintype "passive"))
      (node (ref "X201") (pin "GND") (pinfunction "GND_GND") (pintype "passive"))
    )
    (net (code "10") (name "GNDIO") (class "Default")
      (node (ref "R317") (pin "1") (pinfunction "1_1") (pintype "passive"))
      (node (ref "R318") (pin "1") (pinfunction "1_1") (pintype "passive"))
      (node (ref "R319") (pin "1") (pinfunction "1_1") (pintype "passive"))
      (node (ref "R320") (pin "1") (pinfunction "1_1") (pintype "passive"))
      (node (ref "R321") (pin "1") (pinfunction "1_1") (pintype "passive"))
      (node (ref "R322") (pin "1") (pinfunction "1_1") (pintype "passive"))
      (node (ref "R323") (pin "1") (pinfunction "1_1") (pintype "passive"))
      (node (ref "R324") (pin "1") (pinfunction "1_1") (pintype "passive"))
      (node (ref "X301") (pin "1") (pinfunction "A_1") (pintype "passive"))
      (node (ref "X301") (pin "2") (pinfunction "A_2") (pintype "passive"))
    )
    (net (code "11") (name "IN0") (class "Default")
      (node (ref "IC201") (pin "19") (pinfunction "(SCL)PC0_19") (pintype "bidirectional"))
      (node (ref "R301") (pin "2") (pinfunction "2_2") (pintype "passive"))
      (node (ref "T301") (pin "3") (pinfunction "C_3") (pintype "passive"))
    )
    (net (code "12") (name "IN1") (class "Default")
      (node (ref "IC201") (pin "20") (pinfunction "(SDA)PC1_20") (pintype "bidirectional"))
      (node (ref "R302") (pin "2") (pinfunction "2_2") (pintype "passive"))
      (node (ref "T302") (pin "3") (pinfunction "C_3") (pintype "passive"))
    )
    (net (code "13") (name "IN2") (class "Default")
      (node (ref "IC201") (pin "21") (pinfunction "(TCK)PC2_21") (pintype "bidirectional"))
      (node (ref "R303") (pin "2") (pinfunction "2_2") (pintype "passive"))
      (node (ref "T303") (pin "3") (pinfunction "C_3") (pintype "passive"))
    )
    (net (code "14") (name "IN3") (class "Default")
      (node (ref "IC201") (pin "22") (pinfunction "(TMS)PC3_22") (pintype "bidirectional"))
      (node (ref "R304") (pin "2") (pinfunction "2_2") (pintype "passive"))
      (node (ref "T304") (pin "3") (pinfunction "C_3") (pintype "passive"))
    )
    (net (code "15") (name "IN4") (class "Default")
      (node (ref "IC201") (pin "23") (pinfunction "(TDO)PC4_23") (pintype "bidirectional"))
      (node (ref "R305") (pin "2") (pinfunction "2_2") (pintype "passive"))
      (node (ref "T305") (pin "3") (pinfunction "C_3") (pintype "passive"))
    )
    (net (code "16") (name "IN5") (class "Default")
      (node (ref "IC201") (pin "24") (pinfunction "(TDI)PC5_24") (pintype "bidirectional"))
      (node (ref "R306") (pin "2") (pinfunction "2_2") (pintype "passive"))
      (node (ref "T306") (pin "3") (pinfunction "C_3") (pintype "passive"))
    )
    (net (code "17") (name "IN6") (class "Default")
      (node (ref "IC201") (pin "25") (pinfunction "(TOSC1)PC6_25") (pintype "bidirectional"))
      (node (ref "R307") (pin "2") (pinfunction "2_2") (pintype "passive"))
      (node (ref "T307") (pin "3") (pinfunction "C_3") (pintype "passive"))
    )
    (net (code "18") (name "IN7") (class "Default")
      (node (ref "IC201") (pin "26") (pinfunction "(TOSC2)PC7_26") (pintype "bidirectional"))
      (node (ref "R308") (pin "2") (pinfunction "2_2") (pintype "passive"))
      (node (ref "T308") (pin "3") (pinfunction "C_3") (pintype "passive"))
    )
    (net (code "19") (name "MISO") (class "Default")
      (node (ref "IC201") (pin "2") (pinfunction "(MISO)PB6_2") (pintype "bidirectional"))
      (node (ref "X201") (pin "MISO") (pinfunction "MISO_MISO") (pintype "passive"))
    )
    (net (code "20") (name "MOSI") (class "Default")
      (node (ref "IC201") (pin "1") (pinfunction "(MOSI)PB5_1") (pintype "bidirectional"))
      (node (ref "X201") (pin "MOSI") (pinfunction "MOSI_MOSI") (pintype "passive"))
    )
    (net (code "21") (name "Net-(D102-PadA)") (class "Default")
      (node (ref "D102") (pin "A") (pinfunction "A_A") (pintype "passive"))
      (node (ref "R101") (pin "1") (pinfunction "1_1") (pintype "passive"))
    )
    (net (code "22") (name "Net-(D104-PadA)") (class "Default")
      (node (ref "D104") (pin "A") (pinfunction "A_A") (pintype "passive"))
      (node (ref "G102") (pin "P1") (pinfunction "+_P1") (pintype "passive"))
      (node (ref "G102") (pin "P2") (pinfunction "+_P2") (pintype "passive"))
      (node (ref "R102") (pin "2") (pinfunction "2_2") (pintype "passive"))
    )
    (net (code "23") (name "Net-(D201-PadA)") (class "Default")
      (node (ref "D201") (pin "A") (pinfunction "A_A") (pintype "passive"))
      (node (ref "R202") (pin "1") (pinfunction "1_1") (pintype "passive"))
    )
    (net (code "24") (name "Net-(D202-PadA)") (class "Default")
      (node (ref "D202") (pin "A") (pinfunction "A_A") (pintype "passive"))
      (node (ref "R203") (pin "1") (pinfunction "1_1") (pintype "passive"))
    )
    (net (code "25") (name "Net-(D301-PadA)") (class "Default")
      (node (ref "D301") (pin "A") (pinfunction "A_A") (pintype "passive"))
      (node (ref "R301") (pin "1") (pinfunction "1_1") (pintype "passive"))
    )
    (net (code "26") (name "Net-(D302-PadA)") (class "Default")
      (node (ref "D302") (pin "A") (pinfunction "A_A") (pintype "passive"))
      (node (ref "R302") (pin "1") (pinfunction "1_1") (pintype "passive"))
    )
    (net (code "27") (name "Net-(D303-PadA)") (class "Default")
      (node (ref "D303") (pin "A") (pinfunction "A_A") (pintype "passive"))
      (node (ref "R303") (pin "1") (pinfunction "1_1") (pintype "passive"))
    )
    (net (code "28") (name "Net-(D304-PadA)") (class "Default")
      (node (ref "D304") (pin "A") (pinfunction "A_A") (pintype "passive"))
      (node (ref "R304") (pin "1") (pinfunction "1_1") (pintype "passive"))
    )
    (net (code "29") (name "Net-(D305-PadA)") (class "Default")
      (node (ref "D305") (pin "A") (pinfunction "A_A") (pintype "passive"))
      (node (ref "R305") (pin "1") (pinfunction "1_1") (pintype "passive"))
    )
    (net (code "30") (name "Net-(D306-PadA)") (class "Default")
      (node (ref "D306") (pin "A") (pinfunction "A_A") (pintype "passive"))
      (node (ref "R306") (pin "1") (pinfunction "1_1") (pintype "passive"))
    )
    (net (code "31") (name "Net-(D307-PadA)") (class "Default")
      (node (ref "D307") (pin "A") (pinfunction "A_A") (pintype "passive"))
      (node (ref "R307") (pin "1") (pinfunction "1_1") (pintype "passive"))
    )
    (net (code "32") (name "Net-(D308-PadA)") (class "Default")
      (node (ref "D308") (pin "A") (pinfunction "A_A") (pintype "passive"))
      (node (ref "R308") (pin "1") (pinfunction "1_1") (pintype "passive"))
    )
    (net (code "33") (name "Net-(D401-C)") (class "Default")
      (node (ref "D401") (pin "K") (pinfunction "C_K") (pintype "passive"))
      (node (ref "K401") (pin "3") (pinfunction "A_3") (pintype "passive"))
    )
    (net (code "34") (name "Net-(D401-PadA)") (class "Default")
      (node (ref "D401") (pin "A") (pinfunction "A_A") (pintype "passive"))
      (node (ref "R401") (pin "2") (pinfunction "2_2") (pintype "passive"))
    )
    (net (code "35") (name "Net-(D402-C)") (class "Default")
      (node (ref "D402") (pin "K") (pinfunction "C_K") (pintype "passive"))
      (node (ref "K402") (pin "3") (pinfunction "A_3") (pintype "passive"))
    )
    (net (code "36") (name "Net-(D402-PadA)") (class "Default")
      (node (ref "D402") (pin "A") (pinfunction "A_A") (pintype "passive"))
      (node (ref "R402") (pin "2") (pinfunction "2_2") (pintype "passive"))
    )
    (net (code "37") (name "Net-(D403-C)") (class "Default")
      (node (ref "D403") (pin "K") (pinfunction "C_K") (pintype "passive"))
      (node (ref "K403") (pin "3") (pinfunction "A_3") (pintype "passive"))
    )
    (net (code "38") (name "Net-(D403-PadA)") (class "Default")
      (node (ref "D403") (pin "A") (pinfunction "A_A") (pintype "passive"))
      (node (ref "R403") (pin "2") (pinfunction "2_2") (pintype "passive"))
    )
    (net (code "39") (name "Net-(D404-C)") (class "Default")
      (node (ref "D404") (pin "K") (pinfunction "C_K") (pintype "passive"))
      (node (ref "K404") (pin "3") (pinfunction "A_3") (pintype "passive"))
    )
    (net (code "40") (name "Net-(D404-PadA)") (class "Default")
      (node (ref "D404") (pin "A") (pinfunction "A_A") (pintype "passive"))
      (node (ref "R404") (pin "2") (pinfunction "2_2") (pintype "passive"))
    )
    (net (code "41") (name "Net-(D405-C)") (class "Default")
      (node (ref "D405") (pin "K") (pinfunction "C_K") (pintype "passive"))
      (node (ref "K405") (pin "3") (pinfunction "A_3") (pintype "passive"))
    )
    (net (code "42") (name "Net-(D405-PadA)") (class "Default")
      (node (ref "D405") (pin "A") (pinfunction "A_A") (pintype "passive"))
      (node (ref "R405") (pin "2") (pinfunction "2_2") (pintype "passive"))
    )
    (net (code "43") (name "Net-(D406-C)") (class "Default")
      (node (ref "D406") (pin "K") (pinfunction "C_K") (pintype "passive"))
      (node (ref "K406") (pin "3") (pinfunction "A_3") (pintype "passive"))
    )
    (net (code "44") (name "Net-(D406-PadA)") (class "Default")
      (node (ref "D406") (pin "A") (pinfunction "A_A") (pintype "passive"))
      (node (ref "R406") (pin "2") (pinfunction "2_2") (pintype "passive"))
    )
    (net (code "45") (name "Net-(D407-C)") (class "Default")
      (node (ref "D407") (pin "K") (pinfunction "C_K") (pintype "passive"))
      (node (ref "K407") (pin "3") (pinfunction "A_3") (pintype "passive"))
    )
    (net (code "46") (name "Net-(D407-PadA)") (class "Default")
      (node (ref "D407") (pin "A") (pinfunction "A_A") (pintype "passive"))
      (node (ref "R407") (pin "2") (pinfunction "2_2") (pintype "passive"))
    )
    (net (code "47") (name "Net-(D408-C)") (class "Default")
      (node (ref "D408") (pin "K") (pinfunction "C_K") (pintype "passive"))
      (node (ref "K408") (pin "3") (pinfunction "A_3") (pintype "passive"))
    )
    (net (code "48") (name "Net-(D408-PadA)") (class "Default")
      (node (ref "D408") (pin "A") (pinfunction "A_A") (pintype "passive"))
      (node (ref "R408") (pin "2") (pinfunction "2_2") (pintype "passive"))
    )
    (net (code "49") (name "Net-(G101-+VIN)") (class "Default")
      (node (ref "D101") (pin "K") (pinfunction "K_K") (pintype "passive"))
      (node (ref "G101") (pin "2") (pinfunction "+VIN_2") (pintype "passive"))
    )
    (net (code "50") (name "Net-(G101-+VOUT)") (class "Default")
      (node (ref "F101") (pin "2") (pinfunction "2_2") (pintype "passive"))
      (node (ref "G101") (pin "4") (pinfunction "+VOUT_4") (pintype "passive"))
    )
    (net (code "51") (name "Net-(G101--VIN)") (class "Default")
      (node (ref "G101") (pin "1") (pinfunction "-VIN_1") (pintype "passive"))
      (node (ref "X101") (pin "2") (pinfunction "A_2") (pintype "passive"))
    )
    (net (code "52") (name "Net-(IC201-(ADC0)PA0)") (class "Default")
      (node (ref "IC201") (pin "37") (pinfunction "(ADC0)PA0_37") (pintype "bidirectional"))
      (node (ref "R202") (pin "2") (pinfunction "2_2") (pintype "passive"))
    )
    (net (code "53") (name "Net-(IC201-(ADC1)PA1)") (class "Default")
      (node (ref "IC201") (pin "36") (pinfunction "(ADC1)PA1_36") (pintype "bidirectional"))
      (node (ref "R203") (pin "2") (pinfunction "2_2") (pintype "passive"))
    )
    (net (code "54") (name "Net-(IC201-(ADC7)PA7)") (class "Default")
      (node (ref "IC201") (pin "30") (pinfunction "(ADC7)PA7_30") (pintype "bidirectional"))
      (node (ref "R204") (pin "1") (pinfunction "1_1") (pintype "passive"))
      (node (ref "R205") (pin "1") (pinfunction "1_1") (pintype "passive"))
    )
    (net (code "55") (name "Net-(IC201-AREF)") (class "Default")
      (node (ref "C205") (pin "1") (pinfunction "1_1") (pintype "passive"))
      (node (ref "IC201") (pin "29") (pinfunction "AREF_29") (pintype "passive"))
    )
    (net (code "56") (name "Net-(IC201-RESET)") (class "Default")
      (node (ref "IC201") (pin "4") (pinfunction "RESET_4") (pintype "input"))
      (node (ref "R201") (pin "1") (pinfunction "1_1") (pintype "passive"))
      (node (ref "X201") (pin "RESET") (pinfunction "RESET_RESET") (pintype "passive"))
    )
    (net (code "57") (name "Net-(IC202A-X1)") (class "Default")
      (node (ref "IC202") (pin "1") (pinfunction "X1_1") (pintype "bidirectional"))
      (node (ref "Q201") (pin "2") (pinfunction "2_2") (pintype "passive"))
    )
    (net (code "58") (name "Net-(IC202A-X2)") (class "Default")
      (node (ref "IC202") (pin "2") (pinfunction "X2_2") (pintype "bidirectional"))
      (node (ref "Q201") (pin "1") (pinfunction "1_1") (pintype "passive"))
    )
    (net (code "59") (name "Net-(IC202B-VCC)") (class "Default")
      (node (ref "C104") (pin "1") (pinfunction "1_1") (pintype "passive"))
      (node (ref "D103") (pin "K") (pinfunction "K_K") (pintype "passive"))
      (node (ref "D104") (pin "K") (pinfunction "K_K") (pintype "passive"))
      (node (ref "IC202") (pin "8") (pinfunction "VCC_8") (pintype "power_in"))
    )
    (net (code "60") (name "Net-(IC203A-A)") (class "Default")
      (node (ref "IC203") (pin "6") (pinfunction "A_6") (pintype "passive"))
      (node (ref "S201") (pin "84") (pinfunction "4_84") (pintype "passive"))
      (node (ref "X202") (pin "1") (pinfunction "A_1") (pintype "passive"))
    )
    (net (code "61") (name "Net-(IC203A-B)") (class "Default")
      (node (ref "IC203") (pin "7") (pinfunction "B_7") (pintype "passive"))
      (node (ref "R206") (pin "1") (pinfunction "1_1") (pintype "passive"))
      (node (ref "X202") (pin "2") (pinfunction "A_2") (pintype "passive"))
    )
    (net (code "62") (name "Net-(IC204A-A)") (class "Default")
      (node (ref "IC204") (pin "2") (pinfunction "A_2") (pintype "input"))
      (node (ref "R207") (pin "2") (pinfunction "2_2") (pintype "passive"))
      (node (ref "S201") (pin "13") (pinfunction "3_13") (pintype "passive"))
    )
    (net (code "63") (name "Net-(IC204A-B)") (class "Default")
      (node (ref "IC204") (pin "3") (pinfunction "B_3") (pintype "input"))
      (node (ref "R208") (pin "2") (pinfunction "2_2") (pintype "passive"))
      (node (ref "S201") (pin "23") (pinfunction "3_23") (pintype "passive"))
    )
    (net (code "64") (name "Net-(IC204A-C)") (class "Default")
      (node (ref "IC204") (pin "4") (pinfunction "C_4") (pintype "input"))
      (node (ref "R209") (pin "2") (pinfunction "2_2") (pintype "passive"))
      (node (ref "S201") (pin "33") (pinfunction "3_33") (pintype "passive"))
    )
    (net (code "65") (name "Net-(IC204A-D)") (class "Default")
      (node (ref "IC204") (pin "5") (pinfunction "D_5") (pintype "input"))
      (node (ref "R210") (pin "2") (pinfunction "2_2") (pintype "passive"))
      (node (ref "S201") (pin "43") (pinfunction "3_43") (pintype "passive"))
    )
    (net (code "66") (name "Net-(IC204A-E)") (class "Default")
      (node (ref "IC204") (pin "10") (pinfunction "E_10") (pintype "input"))
      (node (ref "R211") (pin "2") (pinfunction "2_2") (pintype "passive"))
      (node (ref "S201") (pin "53") (pinfunction "3_53") (pintype "passive"))
    )
    (net (code "67") (name "Net-(IC204A-F)") (class "Default")
      (node (ref "IC204") (pin "11") (pinfunction "F_11") (pintype "input"))
      (node (ref "R212") (pin "2") (pinfunction "2_2") (pintype "passive"))
      (node (ref "S201") (pin "63") (pinfunction "3_63") (pintype "passive"))
    )
    (net (code "68") (name "Net-(IC204A-G)") (class "Default")
      (node (ref "IC204") (pin "12") (pinfunction "G_12") (pintype "input"))
      (node (ref "R213") (pin "2") (pinfunction "2_2") (pintype "passive"))
      (node (ref "S201") (pin "73") (pinfunction "3_73") (pintype "passive"))
    )
    (net (code "69") (name "Net-(IC301-A)") (class "Default")
      (node (ref "IC301") (pin "1") (pinfunction "A_1") (pintype "passive"))
      (node (ref "R309") (pin "1") (pinfunction "1_1") (pintype "passive"))
    )
    (net (code "70") (name "Net-(IC301-C)") (class "Default")
      (node (ref "IC301") (pin "4") (pinfunction "C_4") (pintype "passive"))
      (node (ref "T301") (pin "1") (pinfunction "B_1") (pintype "passive"))
    )
    (net (code "71") (name "Net-(IC301-K)") (class "Default")
      (node (ref "IC301") (pin "2") (pinfunction "K_2") (pintype "passive"))
      (node (ref "R317") (pin "2") (pinfunction "2_2") (pintype "passive"))
    )
    (net (code "72") (name "Net-(IC302-A)") (class "Default")
      (node (ref "IC302") (pin "1") (pinfunction "A_1") (pintype "passive"))
      (node (ref "R310") (pin "1") (pinfunction "1_1") (pintype "passive"))
    )
    (net (code "73") (name "Net-(IC302-C)") (class "Default")
      (node (ref "IC302") (pin "4") (pinfunction "C_4") (pintype "passive"))
      (node (ref "T302") (pin "1") (pinfunction "B_1") (pintype "passive"))
    )
    (net (code "74") (name "Net-(IC302-K)") (class "Default")
      (node (ref "IC302") (pin "2") (pinfunction "K_2") (pintype "passive"))
      (node (ref "R318") (pin "2") (pinfunction "2_2") (pintype "passive"))
    )
    (net (code "75") (name "Net-(IC303-A)") (class "Default")
      (node (ref "IC303") (pin "1") (pinfunction "A_1") (pintype "passive"))
      (node (ref "R311") (pin "1") (pinfunction "1_1") (pintype "passive"))
    )
    (net (code "76") (name "Net-(IC303-C)") (class "Default")
      (node (ref "IC303") (pin "4") (pinfunction "C_4") (pintype "passive"))
      (node (ref "T303") (pin "1") (pinfunction "B_1") (pintype "passive"))
    )
    (net (code "77") (name "Net-(IC303-K)") (class "Default")
      (node (ref "IC303") (pin "2") (pinfunction "K_2") (pintype "passive"))
      (node (ref "R319") (pin "2") (pinfunction "2_2") (pintype "passive"))
    )
    (net (code "78") (name "Net-(IC304-A)") (class "Default")
      (node (ref "IC304") (pin "1") (pinfunction "A_1") (pintype "passive"))
      (node (ref "R312") (pin "1") (pinfunction "1_1") (pintype "passive"))
    )
    (net (code "79") (name "Net-(IC304-C)") (class "Default")
      (node (ref "IC304") (pin "4") (pinfunction "C_4") (pintype "passive"))
      (node (ref "T304") (pin "1") (pinfunction "B_1") (pintype "passive"))
    )
    (net (code "80") (name "Net-(IC304-K)") (class "Default")
      (node (ref "IC304") (pin "2") (pinfunction "K_2") (pintype "passive"))
      (node (ref "R320") (pin "2") (pinfunction "2_2") (pintype "passive"))
    )
    (net (code "81") (name "Net-(IC305-A)") (class "Default")
      (node (ref "IC305") (pin "1") (pinfunction "A_1") (pintype "passive"))
      (node (ref "R313") (pin "1") (pinfunction "1_1") (pintype "passive"))
    )
    (net (code "82") (name "Net-(IC305-C)") (class "Default")
      (node (ref "IC305") (pin "4") (pinfunction "C_4") (pintype "passive"))
      (node (ref "T305") (pin "1") (pinfunction "B_1") (pintype "passive"))
    )
    (net (code "83") (name "Net-(IC305-K)") (class "Default")
      (node (ref "IC305") (pin "2") (pinfunction "K_2") (pintype "passive"))
      (node (ref "R321") (pin "2") (pinfunction "2_2") (pintype "passive"))
    )
    (net (code "84") (name "Net-(IC306-A)") (class "Default")
      (node (ref "IC306") (pin "1") (pinfunction "A_1") (pintype "passive"))
      (node (ref "R314") (pin "1") (pinfunction "1_1") (pintype "passive"))
    )
    (net (code "85") (name "Net-(IC306-C)") (class "Default")
      (node (ref "IC306") (pin "4") (pinfunction "C_4") (pintype "passive"))
      (node (ref "T306") (pin "1") (pinfunction "B_1") (pintype "passive"))
    )
    (net (code "86") (name "Net-(IC306-K)") (class "Default")
      (node (ref "IC306") (pin "2") (pinfunction "K_2") (pintype "passive"))
      (node (ref "R322") (pin "2") (pinfunction "2_2") (pintype "passive"))
    )
    (net (code "87") (name "Net-(IC307-A)") (class "Default")
      (node (ref "IC307") (pin "1") (pinfunction "A_1") (pintype "passive"))
      (node (ref "R315") (pin "1") (pinfunction "1_1") (pintype "passive"))
    )
    (net (code "88") (name "Net-(IC307-C)") (class "Default")
      (node (ref "IC307") (pin "4") (pinfunction "C_4") (pintype "passive"))
      (node (ref "T307") (pin "1") (pinfunction "B_1") (pintype "passive"))
    )
    (net (code "89") (name "Net-(IC307-K)") (class "Default")
      (node (ref "IC307") (pin "2") (pinfunction "K_2") (pintype "passive"))
      (node (ref "R323") (pin "2") (pinfunction "2_2") (pintype "passive"))
    )
    (net (code "90") (name "Net-(IC308-A)") (class "Default")
      (node (ref "IC308") (pin "1") (pinfunction "A_1") (pintype "passive"))
      (node (ref "R316") (pin "1") (pinfunction "1_1") (pintype "passive"))
    )
    (net (code "91") (name "Net-(IC308-C)") (class "Default")
      (node (ref "IC308") (pin "4") (pinfunction "C_4") (pintype "passive"))
      (node (ref "T308") (pin "1") (pinfunction "B_1") (pintype "passive"))
    )
    (net (code "92") (name "Net-(IC308-K)") (class "Default")
      (node (ref "IC308") (pin "2") (pinfunction "K_2") (pintype "passive"))
      (node (ref "R324") (pin "2") (pinfunction "2_2") (pintype "passive"))
    )
    (net (code "93") (name "Net-(IC401A-QA)") (class "Default")
      (node (ref "IC401") (pin "15") (pinfunction "QA_15") (pintype "tri_state"))
      (node (ref "R401") (pin "1") (pinfunction "1_1") (pintype "passive"))
    )
    (net (code "94") (name "Net-(IC401A-QB)") (class "Default")
      (node (ref "IC401") (pin "1") (pinfunction "QB_1") (pintype "tri_state"))
      (node (ref "R402") (pin "1") (pinfunction "1_1") (pintype "passive"))
    )
    (net (code "95") (name "Net-(IC401A-QC)") (class "Default")
      (node (ref "IC401") (pin "2") (pinfunction "QC_2") (pintype "tri_state"))
      (node (ref "R403") (pin "1") (pinfunction "1_1") (pintype "passive"))
    )
    (net (code "96") (name "Net-(IC401A-QD)") (class "Default")
      (node (ref "IC401") (pin "3") (pinfunction "QD_3") (pintype "tri_state"))
      (node (ref "R404") (pin "1") (pinfunction "1_1") (pintype "passive"))
    )
    (net (code "97") (name "Net-(IC401A-QE)") (class "Default")
      (node (ref "IC401") (pin "4") (pinfunction "QE_4") (pintype "tri_state"))
      (node (ref "R405") (pin "1") (pinfunction "1_1") (pintype "passive"))
    )
    (net (code "98") (name "Net-(IC401A-QF)") (class "Default")
      (node (ref "IC401") (pin "5") (pinfunction "QF_5") (pintype "tri_state"))
      (node (ref "R406") (pin "1") (pinfunction "1_1") (pintype "passive"))
    )
    (net (code "99") (name "Net-(IC401A-QG)") (class "Default")
      (node (ref "IC401") (pin "6") (pinfunction "QG_6") (pintype "tri_state"))
      (node (ref "R407") (pin "1") (pinfunction "1_1") (pintype "passive"))
    )
    (net (code "100") (name "Net-(IC401A-QH)") (class "Default")
      (node (ref "IC401") (pin "7") (pinfunction "QH_7") (pintype "tri_state"))
      (node (ref "R408") (pin "1") (pinfunction "1_1") (pintype "passive"))
    )
    (net (code "101") (name "Net-(K401-DS1)") (class "Default")
      (node (ref "K401") (pin "1") (pinfunction "DS1_1") (pintype "passive"))
      (node (ref "X402") (pin "1") (pinfunction "A_1") (pintype "passive"))
    )
    (net (code "102") (name "Net-(K401-DS2)") (class "Default")
      (node (ref "K401") (pin "2") (pinfunction "DS2_2") (pintype "passive"))
      (node (ref "K402") (pin "2") (pinfunction "DS2_2") (pintype "passive"))
      (node (ref "K403") (pin "2") (pinfunction "DS2_2") (pintype "passive"))
      (node (ref "K404") (pin "2") (pinfunction "DS2_2") (pintype "passive"))
      (node (ref "K405") (pin "2") (pinfunction "DS2_2") (pintype "passive"))
      (node (ref "K406") (pin "2") (pinfunction "DS2_2") (pintype "passive"))
      (node (ref "K407") (pin "2") (pinfunction "DS2_2") (pintype "passive"))
      (node (ref "K408") (pin "2") (pinfunction "DS2_2") (pintype "passive"))
      (node (ref "X401") (pin "1") (pinfunction "A_1") (pintype "passive"))
      (node (ref "X401") (pin "2") (pinfunction "A_2") (pintype "passive"))
    )
    (net (code "103") (name "Net-(K402-DS1)") (class "Default")
      (node (ref "K402") (pin "1") (pinfunction "DS1_1") (pintype "passive"))
      (node (ref "X402") (pin "2") (pinfunction "A_2") (pintype "passive"))
    )
    (net (code "104") (name "Net-(K403-DS1)") (class "Default")
      (node (ref "K403") (pin "1") (pinfunction "DS1_1") (pintype "passive"))
      (node (ref "X403") (pin "1") (pinfunction "A_1") (pintype "passive"))
    )
    (net (code "105") (name "Net-(K404-DS1)") (class "Default")
      (node (ref "K404") (pin "1") (pinfunction "DS1_1") (pintype "passive"))
      (node (ref "X403") (pin "2") (pinfunction "A_2") (pintype "passive"))
    )
    (net (code "106") (name "Net-(K405-DS1)") (class "Default")
      (node (ref "K405") (pin "1") (pinfunction "DS1_1") (pintype "passive"))
      (node (ref "X404") (pin "1") (pinfunction "A_1") (pintype "passive"))
    )
    (net (code "107") (name "Net-(K406-DS1)") (class "Default")
      (node (ref "K406") (pin "1") (pinfunction "DS1_1") (pintype "passive"))
      (node (ref "X404") (pin "2") (pinfunction "A_2") (pintype "passive"))
    )
    (net (code "108") (name "Net-(K407-DS1)") (class "Default")
      (node (ref "K407") (pin "1") (pinfunction "DS1_1") (pintype "passive"))
      (node (ref "X405") (pin "1") (pinfunction "A_1") (pintype "passive"))
    )
    (net (code "109") (name "Net-(K408-DS1)") (class "Default")
      (node (ref "K408") (pin "1") (pinfunction "DS1_1") (pintype "passive"))
      (node (ref "X405") (pin "2") (pinfunction "A_2") (pintype "passive"))
    )
    (net (code "110") (name "Net-(S201H-3)") (class "Default")
      (node (ref "R206") (pin "2") (pinfunction "2_2") (pintype "passive"))
      (node (ref "S201") (pin "83") (pinfunction "3_83") (pintype "passive"))
    )
    (net (code "111") (name "Net-(X101A-A)") (class "Default")
      (node (ref "D101") (pin "A") (pinfunction "A_A") (pintype "passive"))
      (node (ref "X101") (pin "1") (pinfunction "A_1") (pintype "passive"))
    )
    (net (code "112") (name "Net-(X302A-A)") (class "Default")
      (node (ref "R310") (pin "2") (pinfunction "2_2") (pintype "passive"))
      (node (ref "X302") (pin "1") (pinfunction "A_1") (pintype "passive"))
    )
    (net (code "113") (name "Net-(X302B-A)") (class "Default")
      (node (ref "R309") (pin "2") (pinfunction "2_2") (pintype "passive"))
      (node (ref "X302") (pin "2") (pinfunction "A_2") (pintype "passive"))
    )
    (net (code "114") (name "Net-(X303A-A)") (class "Default")
      (node (ref "R312") (pin "2") (pinfunction "2_2") (pintype "passive"))
      (node (ref "X303") (pin "1") (pinfunction "A_1") (pintype "passive"))
    )
    (net (code "115") (name "Net-(X303B-A)") (class "Default")
      (node (ref "R311") (pin "2") (pinfunction "2_2") (pintype "passive"))
      (node (ref "X303") (pin "2") (pinfunction "A_2") (pintype "passive"))
    )
    (net (code "116") (name "Net-(X304A-A)") (class "Default")
      (node (ref "R314") (pin "2") (pinfunction "2_2") (pintype "passive"))
      (node (ref "X304") (pin "1") (pinfunction "A_1") (pintype "passive"))
    )
    (net (code "117") (name "Net-(X304B-A)") (class "Default")
      (node (ref "R313") (pin "2") (pinfunction "2_2") (pintype "passive"))
      (node (ref "X304") (pin "2") (pinfunction "A_2") (pintype "passive"))
    )
    (net (code "118") (name "Net-(X305A-A)") (class "Default")
      (node (ref "R316") (pin "2") (pinfunction "2_2") (pintype "passive"))
      (node (ref "X305") (pin "1") (pinfunction "A_1") (pintype "passive"))
    )
    (net (code "119") (name "Net-(X305B-A)") (class "Default")
      (node (ref "R315") (pin "2") (pinfunction "2_2") (pintype "passive"))
      (node (ref "X305") (pin "2") (pinfunction "A_2") (pintype "passive"))
    )
    (net (code "120") (name "RE") (class "Default")
      (node (ref "IC201") (pin "14") (pinfunction "(OC1A)PD5_14") (pintype "bidirectional"))
      (node (ref "IC203") (pin "2") (pinfunction "RE/_2") (pintype "input"))
    )
    (net (code "121") (name "RXD") (class "Default")
      (node (ref "IC201") (pin "9") (pinfunction "(RXD)PD0_9") (pintype "bidirectional"))
      (node (ref "IC203") (pin "1") (pinfunction "RO_1") (pintype "output"))
    )
    (net (code "122") (name "SCK") (class "Default")
      (node (ref "IC201") (pin "3") (pinfunction "(SCK)PB7_3") (pintype "bidirectional"))
      (node (ref "X201") (pin "SCK") (pinfunction "SCK_SCK") (pintype "passive"))
    )
    (net (code "123") (name "SCL") (class "Default")
      (node (ref "IC201") (pin "15") (pinfunction "(ICP)PD6_15") (pintype "bidirectional"))
      (node (ref "IC202") (pin "6") (pinfunction "SCL_6") (pintype "bidirectional"))
    )
    (net (code "124") (name "SDA") (class "Default")
      (node (ref "IC201") (pin "16") (pinfunction "(OC2)PD7_16") (pintype "bidirectional"))
      (node (ref "IC202") (pin "5") (pinfunction "SDA_5") (pintype "bidirectional"))
    )
    (net (code "125") (name "TE") (class "Default")
      (node (ref "IC201") (pin "13") (pinfunction "(OC1B)PD4_13") (pintype "bidirectional"))
      (node (ref "IC203") (pin "3") (pinfunction "DE_3") (pintype "input"))
    )
    (net (code "126") (name "TXD") (class "Default")
      (node (ref "IC201") (pin "10") (pinfunction "(TXD)PD1_10") (pintype "bidirectional"))
      (node (ref "IC203") (pin "4") (pinfunction "DI_4") (pintype "input"))
    )
    (net (code "127") (name "unconnected-(IC201-(ADC2)PA2-Pad35)") (class "Default")
      (node (ref "IC201") (pin "35") (pinfunction "(ADC2)PA2_35") (pintype "bidirectional"))
    )
    (net (code "128") (name "unconnected-(IC201-(ADC3)PA3-Pad34)") (class "Default")
      (node (ref "IC201") (pin "34") (pinfunction "(ADC3)PA3_34") (pintype "bidirectional"))
    )
    (net (code "129") (name "unconnected-(IC201-(ADC4)PA4-Pad33)") (class "Default")
      (node (ref "IC201") (pin "33") (pinfunction "(ADC4)PA4_33") (pintype "bidirectional"))
    )
    (net (code "130") (name "unconnected-(IC201-(ADC5)PA5-Pad32)") (class "Default")
      (node (ref "IC201") (pin "32") (pinfunction "(ADC5)PA5_32") (pintype "bidirectional"))
    )
    (net (code "131") (name "unconnected-(IC201-XTAL1-Pad8)") (class "Default")
      (node (ref "IC201") (pin "8") (pinfunction "XTAL1_8") (pintype "bidirectional"))
    )
    (net (code "132") (name "unconnected-(IC201-XTAL2-Pad7)") (class "Default")
      (node (ref "IC201") (pin "7") (pinfunction "XTAL2_7") (pintype "bidirectional"))
    )
    (net (code "133") (name "unconnected-(IC401A-QH*-Pad9)") (class "Default")
      (node (ref "IC401") (pin "9") (pinfunction "QH*_9") (pintype "tri_state"))
    )
    (net (code "134") (name "~{R}") (class "Default")
      (node (ref "IC201") (pin "40") (pinfunction "(T0/XCK)PB0_40") (pintype "bidirectional"))
      (node (ref "IC204") (pin "9") (pinfunction "~{CLR}_9") (pintype "input"))
      (node (ref "IC401") (pin "10") (pinfunction "~{SCLR}_10") (pintype "input"))
    )
  )
)
